# Debug_UART.net
KiCad netlist of a schematic drawn in Altium Designer
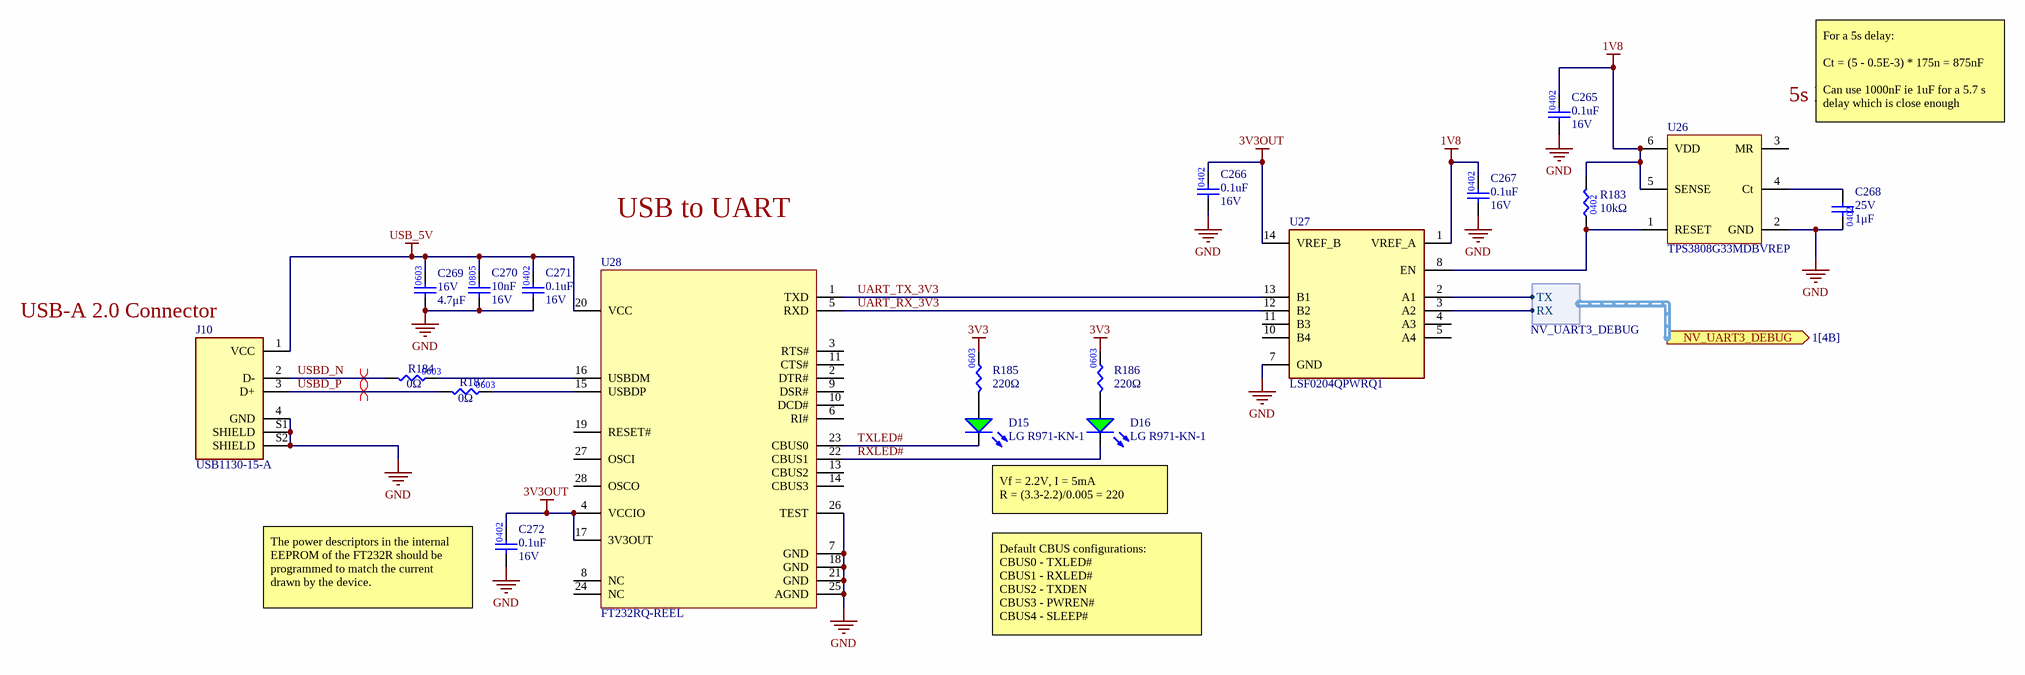
[diagram p0: Debug UART.SchDoc]

(export (version "E")
  (design (tool "Eeschema 10.0.6"))
  (components
    (comp (ref "C265")
      (value "CAP_0.1uF_16V_X7R_0402")
      (footprint "CAP0402")
      (description "CAP CER 0.1UF 16V X7R 0402")
      (fields (field (name "CAPACITANCE") "0.1uF") (field (name "VOLTAGE RATING") "16V"))
      (libsource (lib "UWRT_Schematic_Library_2020") (part "CAP_0.1uF_16V_X7R_0402"))
    )
    (comp (ref "C266")
      (value "CAP_0.1uF_16V_X7R_0402")
      (footprint "CAP0402")
      (description "CAP CER 0.1UF 16V X7R 0402")
      (fields (field (name "CAPACITANCE") "0.1uF") (field (name "VOLTAGE RATING") "16V"))
      (libsource (lib "UWRT_Schematic_Library_2020") (part "CAP_0.1uF_16V_X7R_0402"))
    )
    (comp (ref "C267")
      (value "CAP_0.1uF_16V_X7R_0402")
      (footprint "CAP0402")
      (description "CAP CER 0.1UF 16V X7R 0402")
      (fields (field (name "CAPACITANCE") "0.1uF") (field (name "VOLTAGE RATING") "16V"))
      (libsource (lib "UWRT_Schematic_Library_2020") (part "CAP_0.1uF_16V_X7R_0402"))
    )
    (comp (ref "C268")
      (value "1μF")
      (footprint "CAP0402")
      (description "CAP CER 1UF 25V X5R 0402")
      (fields (field (name "VOLTAGE") "25V") (field (name "Comment") "CAP_1uF_25V_0402"))
      (libsource (lib "UWRT_Schematic_Library_2020") (part "CAP_1uF_25V_0402"))
    )
    (comp (ref "C269")
      (value "4.7μF")
      (footprint "CAP0603")
      (description "CAP CER 4.7UF 16V X6S 0603")
      (fields (field (name "VOLTAGE RATING") "16V") (field (name "Comment") "CAP_4.7uF_16V_0603"))
      (libsource (lib "UWRT_Schematic_Library_2020") (part "CAP_4.7uF_16V_0603"))
    )
    (comp (ref "C270")
      (value "10nF")
      (footprint "CAP2012")
      (description "CAP CER 10000PF 16V X7R 0805")
      (fields (field (name "VOLTAGE RATING") "16V") (field (name "Comment") "CAP_10nF_16V_0805"))
      (libsource (lib "UWRT_Schematic_Library_2020") (part "CAP_10nF_16V_0805"))
    )
    (comp (ref "C271")
      (value "CAP_0.1uF_16V_X7R_0402")
      (footprint "CAP0402")
      (description "CAP CER 0.1UF 16V X7R 0402")
      (fields (field (name "CAPACITANCE") "0.1uF") (field (name "VOLTAGE RATING") "16V"))
      (libsource (lib "UWRT_Schematic_Library_2020") (part "CAP_0.1uF_16V_X7R_0402"))
    )
    (comp (ref "C272")
      (value "CAP_0.1uF_16V_X7R_0402")
      (footprint "CAP0402")
      (description "CAP CER 0.1UF 16V X7R 0402")
      (fields (field (name "CAPACITANCE") "0.1uF") (field (name "VOLTAGE RATING") "16V"))
      (libsource (lib "UWRT_Schematic_Library_2020") (part "CAP_0.1uF_16V_X7R_0402"))
    )
    (comp (ref "D15")
      (value "LED_GREEN")
      (footprint "LED_0805_GREEN")
      (description "LED GREEN DIFFUSED 0805 SMD")
      (fields (field (name "MANUFACTURER PART NUMBER 1") "LG R971-KN-1"))
      (libsource (lib "UWRT_Schematic_Library_2020") (part "LED_GREEN"))
    )
    (comp (ref "D16")
      (value "LED_GREEN")
      (footprint "LED_0805_GREEN")
      (description "LED GREEN DIFFUSED 0805 SMD")
      (fields (field (name "MANUFACTURER PART NUMBER 1") "LG R971-KN-1"))
      (libsource (lib "UWRT_Schematic_Library_2020") (part "LED_GREEN"))
    )
    (comp (ref "J10")
      (value "USB-A 2.0 Connector")
      (footprint "USB-A 2.0 Connector")
      (description "USB-A (USB TYPE-A) USB 2.0 Receptacle Connector 4 Position Through Hole, Right Angle")
      (fields (field (name "MANUFACTURER PART NUMBER 1") "USB1130-15-A"))
      (libsource (lib "UWRT_Schematic_Library_2020") (part "USB-A 2.0 Connector"))
    )
    (comp (ref "R183")
      (value "RES_10kΩ_0402_1%")
      (footprint "RES0402")
      (description "RES 10K OHM 1% 1/16W 0402")
      (fields (field (name "TOLERANCE") "1%") (field (name "RESISTANCE") "10kΩ"))
      (libsource (lib "UWRT_Schematic_Library_2020") (part "RES_10kΩ_0402_1%"))
    )
    (comp (ref "R184")
      (value "0Ω")
      (footprint "RES0603")
      (description "RES 0 OHM JUMPER 1/10W 0603")
      (fields (field (name "Comment") "RES_0Ω_0603"))
      (libsource (lib "UWRT_Schematic_Library_2020") (part "RES_0Ω_0603"))
    )
    (comp (ref "R185")
      (value "220Ω")
      (footprint "RES0603")
      (description "RES 220 OHM 5% 1/10W 0603")
      (fields (field (name "Comment") "RES_220Ω_0603"))
      (libsource (lib "UWRT_Schematic_Library_2020") (part "RES_220Ω_0603_5%"))
    )
    (comp (ref "R186")
      (value "220Ω")
      (footprint "RES0603")
      (description "RES 220 OHM 5% 1/10W 0603")
      (fields (field (name "Comment") "RES_220Ω_0603"))
      (libsource (lib "UWRT_Schematic_Library_2020") (part "RES_220Ω_0603_5%"))
    )
    (comp (ref "R187")
      (value "0Ω")
      (footprint "RES0603")
      (description "RES 0 OHM JUMPER 1/10W 0603")
      (fields (field (name "Comment") "RES_0Ω_0603"))
      (libsource (lib "UWRT_Schematic_Library_2020") (part "RES_0Ω_0603"))
    )
    (comp (ref "U26")
      (value "TPS3808G33MDBVREP")
      (footprint "TPS3808G33MDBVREP")
      (description "IC SUPERVISOR 1 CHANNEL SOT23-6")
      (fields (field (name "MANUFACTURER PART NUMBER 1") "TPS3808G33MDBVREP"))
      (libsource (lib "UWRT_Schematic_Library_2020") (part "TPS3808G33MDBVREP"))
    )
    (comp (ref "U27")
      (value "LSF0204QPWRQ1")
      (footprint "SOP65P640X120-14N")
      (description "4-BITS MULTI-VOLTAGE LEVEL TRANS")
      (libsource (lib "UWRT_Schematic_Library_2020") (part "LSF0204QPWRQ1"))
    )
    (comp (ref "U28")
      (value "FT232RQ-REEL")
      (footprint "FT232RQ-REEL_FTD")
      (description "USB Bridge, USB to UART USB 2.0 UART Interface 32-QFN (5x5)")
      (fields (field (name "MANUFACTURER") "FTDI") (field (name "MANUFACTURER PART NUMBER") "FT232RQ-REEL"))
      (libsource (lib "UWRT_Schematic_Library_2020") (part "FT232RQ-REEL"))
    )
  )
  (nets
    (net (code "2") (name "/RX") (class "Default")
      (node (ref "U27") (pin "3") (pinfunction "A2_3") (pintype "passive"))
    )
    (net (code "3") (name "/RXLED#") (class "Default")
      (node (ref "D16") (pin "2") (pinfunction "K_2") (pintype "passive"))
      (node (ref "U28") (pin "22") (pinfunction "CBUS1_22") (pintype "passive"))
    )
    (net (code "4") (name "/TX") (class "Default")
      (node (ref "U27") (pin "2") (pinfunction "A1_2") (pintype "passive"))
    )
    (net (code "5") (name "/TXLED#") (class "Default")
      (node (ref "D15") (pin "2") (pinfunction "K_2") (pintype "passive"))
      (node (ref "U28") (pin "23") (pinfunction "CBUS0_23") (pintype "passive"))
    )
    (net (code "6") (name "/UART_RX_3V3") (class "Default")
      (node (ref "U27") (pin "12") (pinfunction "B2_12") (pintype "passive"))
      (node (ref "U28") (pin "5") (pinfunction "RXD_5") (pintype "passive"))
    )
    (net (code "7") (name "/UART_TX_3V3") (class "Default")
      (node (ref "U27") (pin "13") (pinfunction "B1_13") (pintype "passive"))
      (node (ref "U28") (pin "1") (pinfunction "TXD_1") (pintype "passive"))
    )
    (net (code "8") (name "/USBD_N") (class "Default")
      (node (ref "J10") (pin "2") (pinfunction "D-_2") (pintype "passive"))
      (node (ref "R184") (pin "1") (pinfunction "1_1") (pintype "passive"))
    )
    (net (code "9") (name "/USBD_P") (class "Default")
      (node (ref "J10") (pin "3") (pinfunction "D+_3") (pintype "passive"))
      (node (ref "R187") (pin "1") (pinfunction "1_1") (pintype "passive"))
    )
    (net (code "11") (name "1V8") (class "Default")
      (node (ref "C265") (pin "2") (pinfunction "2_2") (pintype "passive"))
      (node (ref "C267") (pin "2") (pinfunction "2_2") (pintype "passive"))
      (node (ref "R183") (pin "2") (pinfunction "2_2") (pintype "passive"))
      (node (ref "U26") (pin "5") (pinfunction "SENSE_5") (pintype "passive"))
      (node (ref "U26") (pin "6") (pinfunction "VDD_6") (pintype "passive"))
      (node (ref "U27") (pin "1") (pinfunction "VREF_A_1") (pintype "passive"))
    )
    (net (code "12") (name "3V3") (class "Default")
      (node (ref "R185") (pin "2") (pinfunction "2_2") (pintype "passive"))
      (node (ref "R186") (pin "2") (pinfunction "2_2") (pintype "passive"))
    )
    (net (code "13") (name "3V3OUT") (class "Default")
      (node (ref "C266") (pin "2") (pinfunction "2_2") (pintype "passive"))
      (node (ref "C272") (pin "2") (pinfunction "2_2") (pintype "passive"))
      (node (ref "U27") (pin "14") (pinfunction "VREF_B_14") (pintype "passive"))
      (node (ref "U28") (pin "17") (pinfunction "3V3OUT_17") (pintype "passive"))
      (node (ref "U28") (pin "4") (pinfunction "VCCIO_4") (pintype "passive"))
    )
    (net (code "14") (name "GND") (class "Default")
      (node (ref "C265") (pin "1") (pinfunction "1_1") (pintype "passive"))
      (node (ref "C266") (pin "1") (pinfunction "1_1") (pintype "passive"))
      (node (ref "C267") (pin "1") (pinfunction "1_1") (pintype "passive"))
      (node (ref "C268") (pin "1") (pinfunction "1_1") (pintype "passive"))
      (node (ref "C269") (pin "1") (pinfunction "1_1") (pintype "passive"))
      (node (ref "C270") (pin "1") (pinfunction "1_1") (pintype "passive"))
      (node (ref "C271") (pin "1") (pinfunction "1_1") (pintype "passive"))
      (node (ref "C272") (pin "1") (pinfunction "1_1") (pintype "passive"))
      (node (ref "J10") (pin "4") (pinfunction "GND_4") (pintype "passive"))
      (node (ref "J10") (pin "S1") (pinfunction "SHIELD_S1") (pintype "passive"))
      (node (ref "J10") (pin "S2") (pinfunction "SHIELD_S2") (pintype "passive"))
      (node (ref "U26") (pin "2") (pinfunction "GND_2") (pintype "passive"))
      (node (ref "U27") (pin "7") (pinfunction "GND_7") (pintype "passive"))
      (node (ref "U28") (pin "18") (pinfunction "GND_18") (pintype "passive"))
      (node (ref "U28") (pin "21") (pinfunction "GND_21") (pintype "passive"))
      (node (ref "U28") (pin "25") (pinfunction "AGND_25") (pintype "passive"))
      (node (ref "U28") (pin "26") (pinfunction "TEST_26") (pintype "passive"))
      (node (ref "U28") (pin "7") (pinfunction "GND_7") (pintype "passive"))
    )
    (net (code "15") (name "Net-(D15-A)") (class "Default")
      (node (ref "D15") (pin "1") (pinfunction "A_1") (pintype "passive"))
      (node (ref "R185") (pin "1") (pinfunction "1_1") (pintype "passive"))
    )
    (net (code "16") (name "Net-(D16-A)") (class "Default")
      (node (ref "D16") (pin "1") (pinfunction "A_1") (pintype "passive"))
      (node (ref "R186") (pin "1") (pinfunction "1_1") (pintype "passive"))
    )
    (net (code "17") (name "Net-(U26-Ct)") (class "Default")
      (node (ref "C268") (pin "2") (pinfunction "2_2") (pintype "passive"))
      (node (ref "U26") (pin "4") (pinfunction "Ct_4") (pintype "passive"))
    )
    (net (code "18") (name "Net-(U26-RESET)") (class "Default")
      (node (ref "R183") (pin "1") (pinfunction "1_1") (pintype "passive"))
      (node (ref "U26") (pin "1") (pinfunction "RESET_1") (pintype "passive"))
      (node (ref "U27") (pin "8") (pinfunction "EN_8") (pintype "passive"))
    )
    (net (code "19") (name "Net-(U28-USBDM)") (class "Default")
      (node (ref "R184") (pin "2") (pinfunction "2_2") (pintype "passive"))
      (node (ref "U28") (pin "16") (pinfunction "USBDM_16") (pintype "passive"))
    )
    (net (code "20") (name "Net-(U28-USBDP)") (class "Default")
      (node (ref "R187") (pin "2") (pinfunction "2_2") (pintype "passive"))
      (node (ref "U28") (pin "15") (pinfunction "USBDP_15") (pintype "passive"))
    )
    (net (code "21") (name "USB_5V") (class "Default")
      (node (ref "C269") (pin "2") (pinfunction "2_2") (pintype "passive"))
      (node (ref "C270") (pin "2") (pinfunction "2_2") (pintype "passive"))
      (node (ref "C271") (pin "2") (pinfunction "2_2") (pintype "passive"))
      (node (ref "J10") (pin "1") (pinfunction "VCC_1") (pintype "passive"))
      (node (ref "U28") (pin "20") (pinfunction "VCC_20") (pintype "passive"))
    )
    (net (code "22") (name "unconnected-(U26-MR-Pad3)") (class "Default")
      (node (ref "U26") (pin "3") (pinfunction "MR_3") (pintype "passive"))
    )
    (net (code "23") (name "unconnected-(U27-A3-Pad4)") (class "Default")
      (node (ref "U27") (pin "4") (pinfunction "A3_4") (pintype "passive"))
    )
    (net (code "24") (name "unconnected-(U27-A4-Pad5)") (class "Default")
      (node (ref "U27") (pin "5") (pinfunction "A4_5") (pintype "passive"))
    )
    (net (code "25") (name "unconnected-(U27-B3-Pad11)") (class "Default")
      (node (ref "U27") (pin "11") (pinfunction "B3_11") (pintype "passive"))
    )
    (net (code "26") (name "unconnected-(U27-B4-Pad10)") (class "Default")
      (node (ref "U27") (pin "10") (pinfunction "B4_10") (pintype "passive"))
    )
    (net (code "27") (name "unconnected-(U28-CBUS2-Pad13)") (class "Default")
      (node (ref "U28") (pin "13") (pinfunction "CBUS2_13") (pintype "passive"))
    )
    (net (code "28") (name "unconnected-(U28-CBUS3-Pad14)") (class "Default")
      (node (ref "U28") (pin "14") (pinfunction "CBUS3_14") (pintype "passive"))
    )
    (net (code "29") (name "unconnected-(U28-CTS#-Pad11)") (class "Default")
      (node (ref "U28") (pin "11") (pinfunction "CTS#_11") (pintype "passive"))
    )
    (net (code "30") (name "unconnected-(U28-DCD#-Pad10)") (class "Default")
      (node (ref "U28") (pin "10") (pinfunction "DCD#_10") (pintype "passive"))
    )
    (net (code "31") (name "unconnected-(U28-DSR#-Pad9)") (class "Default")
      (node (ref "U28") (pin "9") (pinfunction "DSR#_9") (pintype "passive"))
    )
    (net (code "32") (name "unconnected-(U28-DTR#-Pad2)") (class "Default")
      (node (ref "U28") (pin "2") (pinfunction "DTR#_2") (pintype "passive"))
    )
    (net (code "33") (name "unconnected-(U28-NC-Pad8)") (class "Default")
      (node (ref "U28") (pin "8") (pinfunction "NC_8") (pintype "passive"))
    )
    (net (code "34") (name "unconnected-(U28-NC-Pad24)") (class "Default")
      (node (ref "U28") (pin "24") (pinfunction "NC_24") (pintype "passive"))
    )
    (net (code "35") (name "unconnected-(U28-OSCI-Pad27)") (class "Default")
      (node (ref "U28") (pin "27") (pinfunction "OSCI_27") (pintype "passive"))
    )
    (net (code "36") (name "unconnected-(U28-OSCO-Pad28)") (class "Default")
      (node (ref "U28") (pin "28") (pinfunction "OSCO_28") (pintype "passive"))
    )
    (net (code "37") (name "unconnected-(U28-RESET#-Pad19)") (class "Default")
      (node (ref "U28") (pin "19") (pinfunction "RESET#_19") (pintype "passive"))
    )
    (net (code "38") (name "unconnected-(U28-RI#-Pad6)") (class "Default")
      (node (ref "U28") (pin "6") (pinfunction "RI#_6") (pintype "passive"))
    )
    (net (code "39") (name "unconnected-(U28-RTS#-Pad3)") (class "Default")
      (node (ref "U28") (pin "3") (pinfunction "RTS#_3") (pintype "passive"))
    )
  )
)
